# Power_Stuff.net
KiCad netlist of a schematic drawn in Altium Designer
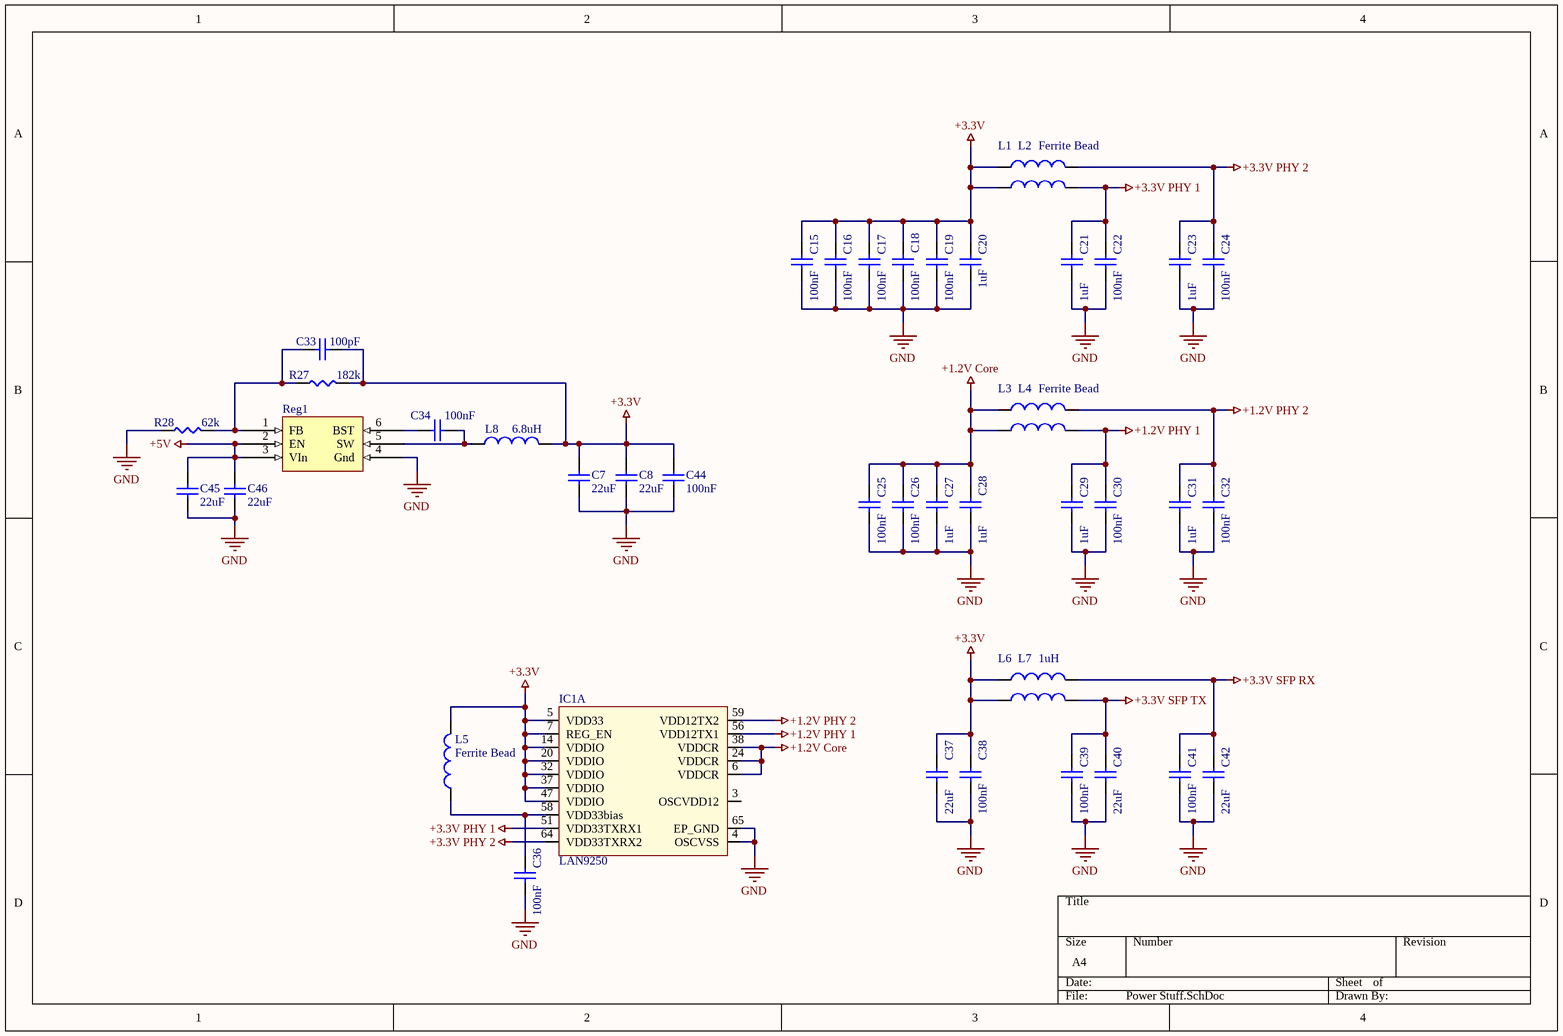
[diagram p0: Power Stuff.SchDoc]

(export (version "E")
  (design (tool "Eeschema 10.0.6"))
  (components
    (comp (ref "C7") (value "22uF") (footprint "0603") (libsource (lib "stdLib") (part "Cap")))
    (comp (ref "C8") (value "22uF") (footprint "0603") (libsource (lib "stdLib") (part "Cap")))
    (comp (ref "C15") (value "100nF") (footprint "0402") (libsource (lib "stdLib") (part "Cap")))
    (comp (ref "C16") (value "100nF") (footprint "0402") (libsource (lib "stdLib") (part "Cap")))
    (comp (ref "C17") (value "100nF") (footprint "0402") (libsource (lib "stdLib") (part "Cap")))
    (comp (ref "C18") (value "100nF") (footprint "0402") (libsource (lib "stdLib") (part "Cap")))
    (comp (ref "C19") (value "100nF") (footprint "0402") (libsource (lib "stdLib") (part "Cap")))
    (comp (ref "C20") (value "1uF") (footprint "0402") (libsource (lib "stdLib") (part "Cap")))
    (comp (ref "C21") (value "1uF") (footprint "0402") (libsource (lib "stdLib") (part "Cap")))
    (comp (ref "C22") (value "100nF") (footprint "0402") (libsource (lib "stdLib") (part "Cap")))
    (comp (ref "C23") (value "1uF") (footprint "0402") (libsource (lib "stdLib") (part "Cap")))
    (comp (ref "C24") (value "100nF") (footprint "0402") (libsource (lib "stdLib") (part "Cap")))
    (comp (ref "C25") (value "100nF") (footprint "0402") (libsource (lib "stdLib") (part "Cap")))
    (comp (ref "C26") (value "100nF") (footprint "0402") (libsource (lib "stdLib") (part "Cap")))
    (comp (ref "C27") (value "1uF") (footprint "0402") (libsource (lib "stdLib") (part "Cap")))
    (comp (ref "C28") (value "1uF") (footprint "0402") (libsource (lib "stdLib") (part "Cap")))
    (comp (ref "C29") (value "1uF") (footprint "0402") (libsource (lib "stdLib") (part "Cap")))
    (comp (ref "C30") (value "100nF") (footprint "0402") (libsource (lib "stdLib") (part "Cap")))
    (comp (ref "C31") (value "1uF") (footprint "0402") (libsource (lib "stdLib") (part "Cap")))
    (comp (ref "C32") (value "100nF") (footprint "0402") (libsource (lib "stdLib") (part "Cap")))
    (comp (ref "C33") (value "100pF") (footprint "0402") (libsource (lib "stdLib") (part "Cap")))
    (comp (ref "C34") (value "100nF") (footprint "0402") (libsource (lib "stdLib") (part "Cap")))
    (comp (ref "C36") (value "100nF") (footprint "0402") (libsource (lib "stdLib") (part "Cap")))
    (comp (ref "C37") (value "22uF") (footprint "0603") (libsource (lib "stdLib") (part "Cap")))
    (comp (ref "C38") (value "100nF") (footprint "0402") (libsource (lib "stdLib") (part "Cap")))
    (comp (ref "C39") (value "100nF") (footprint "0402") (libsource (lib "stdLib") (part "Cap")))
    (comp (ref "C40") (value "22uF") (footprint "0603") (libsource (lib "stdLib") (part "Cap")))
    (comp (ref "C41") (value "100nF") (footprint "0402") (libsource (lib "stdLib") (part "Cap")))
    (comp (ref "C42") (value "22uF") (footprint "0603") (libsource (lib "stdLib") (part "Cap")))
    (comp (ref "C44") (value "100nF") (footprint "0402") (libsource (lib "stdLib") (part "Cap")))
    (comp (ref "C45") (value "22uF") (footprint "0603") (libsource (lib "stdLib") (part "Cap")))
    (comp (ref "C46") (value "22uF") (footprint "0603") (libsource (lib "stdLib") (part "Cap")))
    (comp (ref "IC1")
      (value "LAN9250")
      (footprint "QFN64")
      (description "10/100 Ethernet controller & PHY")
      (libsource (lib "stdLib") (part "LAN9250"))
    )
    (comp (ref "L1") (value "Ferrite Bead") (footprint "0402") (libsource (lib "stdLib") (part "Inductor")))
    (comp (ref "L2") (value "Ferrite Bead") (footprint "0402") (libsource (lib "stdLib") (part "Inductor")))
    (comp (ref "L3") (value "Ferrite Bead") (footprint "0402") (libsource (lib "stdLib") (part "Inductor")))
    (comp (ref "L4") (value "Ferrite Bead") (footprint "0402") (libsource (lib "stdLib") (part "Inductor")))
    (comp (ref "L5") (value "Ferrite Bead") (footprint "0402") (libsource (lib "stdLib") (part "Inductor")))
    (comp (ref "L6") (value "1uH") (footprint "0603") (libsource (lib "stdLib") (part "Inductor")))
    (comp (ref "L7") (value "1uH") (footprint "0603") (libsource (lib "stdLib") (part "Inductor")))
    (comp (ref "L8") (value "6.8uH") (footprint "1008") (libsource (lib "stdLib") (part "Inductor")))
    (comp (ref "R27") (value "182k") (footprint "0402") (libsource (lib "stdLib") (part "Resistor")))
    (comp (ref "R28") (value "62k") (footprint "0402") (libsource (lib "stdLib") (part "Resistor")))
    (comp (ref "Reg1")
      (value "Buck regulator")
      (footprint "TSOT26")
      (libsource (lib "stdLib") (part "AP6320"))
    )
  )
  (nets
    (net (code "1") (name "+1.2V Core") (class "Default")
      (node (ref "C25") (pin "1") (pinfunction "1_1") (pintype "passive"))
      (node (ref "C26") (pin "1") (pinfunction "1_1") (pintype "passive"))
      (node (ref "C27") (pin "1") (pinfunction "1_1") (pintype "passive"))
      (node (ref "C28") (pin "1") (pinfunction "1_1") (pintype "passive"))
      (node (ref "IC1") (pin "24") (pinfunction "VDDCR_24") (pintype "passive"))
      (node (ref "IC1") (pin "38") (pinfunction "VDDCR_38") (pintype "passive"))
      (node (ref "IC1") (pin "6") (pinfunction "VDDCR_6") (pintype "passive"))
      (node (ref "L3") (pin "1") (pinfunction "1_1") (pintype "passive"))
      (node (ref "L4") (pin "1") (pinfunction "1_1") (pintype "passive"))
    )
    (net (code "2") (name "+1.2V PHY 1") (class "Default")
      (node (ref "C29") (pin "1") (pinfunction "1_1") (pintype "passive"))
      (node (ref "C30") (pin "1") (pinfunction "1_1") (pintype "passive"))
      (node (ref "IC1") (pin "56") (pinfunction "VDD12TX1_56") (pintype "passive"))
      (node (ref "L4") (pin "2") (pinfunction "2_2") (pintype "passive"))
    )
    (net (code "3") (name "+1.2V PHY 2") (class "Default")
      (node (ref "C31") (pin "1") (pinfunction "1_1") (pintype "passive"))
      (node (ref "C32") (pin "1") (pinfunction "1_1") (pintype "passive"))
      (node (ref "IC1") (pin "59") (pinfunction "VDD12TX2_59") (pintype "passive"))
      (node (ref "L3") (pin "2") (pinfunction "2_2") (pintype "passive"))
    )
    (net (code "4") (name "+3.3V") (class "Default")
      (node (ref "C15") (pin "1") (pinfunction "1_1") (pintype "passive"))
      (node (ref "C16") (pin "1") (pinfunction "1_1") (pintype "passive"))
      (node (ref "C17") (pin "1") (pinfunction "1_1") (pintype "passive"))
      (node (ref "C18") (pin "1") (pinfunction "1_1") (pintype "passive"))
      (node (ref "C19") (pin "1") (pinfunction "1_1") (pintype "passive"))
      (node (ref "C20") (pin "1") (pinfunction "1_1") (pintype "passive"))
      (node (ref "C33") (pin "1") (pinfunction "1_1") (pintype "passive"))
      (node (ref "C37") (pin "1") (pinfunction "1_1") (pintype "passive"))
      (node (ref "C38") (pin "1") (pinfunction "1_1") (pintype "passive"))
      (node (ref "C44") (pin "1") (pinfunction "1_1") (pintype "passive"))
      (node (ref "C7") (pin "1") (pinfunction "1_1") (pintype "passive"))
      (node (ref "C8") (pin "1") (pinfunction "1_1") (pintype "passive"))
      (node (ref "IC1") (pin "14") (pinfunction "VDDIO_14") (pintype "passive"))
      (node (ref "IC1") (pin "20") (pinfunction "VDDIO_20") (pintype "passive"))
      (node (ref "IC1") (pin "32") (pinfunction "VDDIO_32") (pintype "passive"))
      (node (ref "IC1") (pin "37") (pinfunction "VDDIO_37") (pintype "passive"))
      (node (ref "IC1") (pin "47") (pinfunction "VDDIO_47") (pintype "passive"))
      (node (ref "IC1") (pin "5") (pinfunction "VDD33_5") (pintype "passive"))
      (node (ref "IC1") (pin "7") (pinfunction "REG_EN_7") (pintype "passive"))
      (node (ref "L1") (pin "1") (pinfunction "1_1") (pintype "passive"))
      (node (ref "L2") (pin "1") (pinfunction "1_1") (pintype "passive"))
      (node (ref "L5") (pin "2") (pinfunction "2_2") (pintype "passive"))
      (node (ref "L6") (pin "1") (pinfunction "1_1") (pintype "passive"))
      (node (ref "L7") (pin "1") (pinfunction "1_1") (pintype "passive"))
      (node (ref "L8") (pin "2") (pinfunction "2_2") (pintype "passive"))
      (node (ref "R27") (pin "2") (pinfunction "2_2") (pintype "passive"))
    )
    (net (code "5") (name "+3.3V PHY 1") (class "Default")
      (node (ref "C21") (pin "1") (pinfunction "1_1") (pintype "passive"))
      (node (ref "C22") (pin "1") (pinfunction "1_1") (pintype "passive"))
      (node (ref "IC1") (pin "51") (pinfunction "VDD33TXRX1_51") (pintype "passive"))
      (node (ref "L2") (pin "2") (pinfunction "2_2") (pintype "passive"))
    )
    (net (code "6") (name "+3.3V PHY 2") (class "Default")
      (node (ref "C23") (pin "1") (pinfunction "1_1") (pintype "passive"))
      (node (ref "C24") (pin "1") (pinfunction "1_1") (pintype "passive"))
      (node (ref "IC1") (pin "64") (pinfunction "VDD33TXRX2_64") (pintype "passive"))
      (node (ref "L1") (pin "2") (pinfunction "2_2") (pintype "passive"))
    )
    (net (code "7") (name "+3.3V SFP RX") (class "Default")
      (node (ref "C41") (pin "1") (pinfunction "1_1") (pintype "passive"))
      (node (ref "C42") (pin "1") (pinfunction "1_1") (pintype "passive"))
      (node (ref "L6") (pin "2") (pinfunction "2_2") (pintype "passive"))
    )
    (net (code "8") (name "+3.3V SFP TX") (class "Default")
      (node (ref "C39") (pin "1") (pinfunction "1_1") (pintype "passive"))
      (node (ref "C40") (pin "1") (pinfunction "1_1") (pintype "passive"))
      (node (ref "L7") (pin "2") (pinfunction "2_2") (pintype "passive"))
    )
    (net (code "9") (name "+5V") (class "Default")
      (node (ref "C45") (pin "2") (pinfunction "2_2") (pintype "passive"))
      (node (ref "C46") (pin "1") (pinfunction "1_1") (pintype "passive"))
      (node (ref "Reg1") (pin "2") (pinfunction "EN_2") (pintype "input"))
      (node (ref "Reg1") (pin "3") (pinfunction "VIn_3") (pintype "input"))
    )
    (net (code "10") (name "GND") (class "Default")
      (node (ref "C15") (pin "2") (pinfunction "2_2") (pintype "passive"))
      (node (ref "C16") (pin "2") (pinfunction "2_2") (pintype "passive"))
      (node (ref "C17") (pin "2") (pinfunction "2_2") (pintype "passive"))
      (node (ref "C18") (pin "2") (pinfunction "2_2") (pintype "passive"))
      (node (ref "C19") (pin "2") (pinfunction "2_2") (pintype "passive"))
      (node (ref "C20") (pin "2") (pinfunction "2_2") (pintype "passive"))
      (node (ref "C21") (pin "2") (pinfunction "2_2") (pintype "passive"))
      (node (ref "C22") (pin "2") (pinfunction "2_2") (pintype "passive"))
      (node (ref "C23") (pin "2") (pinfunction "2_2") (pintype "passive"))
      (node (ref "C24") (pin "2") (pinfunction "2_2") (pintype "passive"))
      (node (ref "C25") (pin "2") (pinfunction "2_2") (pintype "passive"))
      (node (ref "C26") (pin "2") (pinfunction "2_2") (pintype "passive"))
      (node (ref "C27") (pin "2") (pinfunction "2_2") (pintype "passive"))
      (node (ref "C28") (pin "2") (pinfunction "2_2") (pintype "passive"))
      (node (ref "C29") (pin "2") (pinfunction "2_2") (pintype "passive"))
      (node (ref "C30") (pin "2") (pinfunction "2_2") (pintype "passive"))
      (node (ref "C31") (pin "2") (pinfunction "2_2") (pintype "passive"))
      (node (ref "C32") (pin "2") (pinfunction "2_2") (pintype "passive"))
      (node (ref "C36") (pin "2") (pinfunction "2_2") (pintype "passive"))
      (node (ref "C37") (pin "2") (pinfunction "2_2") (pintype "passive"))
      (node (ref "C38") (pin "2") (pinfunction "2_2") (pintype "passive"))
      (node (ref "C39") (pin "2") (pinfunction "2_2") (pintype "passive"))
      (node (ref "C40") (pin "2") (pinfunction "2_2") (pintype "passive"))
      (node (ref "C41") (pin "2") (pinfunction "2_2") (pintype "passive"))
      (node (ref "C42") (pin "2") (pinfunction "2_2") (pintype "passive"))
      (node (ref "C44") (pin "2") (pinfunction "2_2") (pintype "passive"))
      (node (ref "C45") (pin "1") (pinfunction "1_1") (pintype "passive"))
      (node (ref "C46") (pin "2") (pinfunction "2_2") (pintype "passive"))
      (node (ref "C7") (pin "2") (pinfunction "2_2") (pintype "passive"))
      (node (ref "C8") (pin "2") (pinfunction "2_2") (pintype "passive"))
      (node (ref "IC1") (pin "4") (pinfunction "OSCVSS_4") (pintype "passive"))
      (node (ref "IC1") (pin "65") (pinfunction "EP_GND_65") (pintype "passive"))
      (node (ref "R28") (pin "1") (pinfunction "1_1") (pintype "passive"))
      (node (ref "Reg1") (pin "4") (pinfunction "Gnd_4") (pintype "input"))
    )
    (net (code "11") (name "Net-(IC1A-VDD33bias)") (class "Default")
      (node (ref "C36") (pin "1") (pinfunction "1_1") (pintype "passive"))
      (node (ref "IC1") (pin "58") (pinfunction "VDD33bias_58") (pintype "passive"))
      (node (ref "L5") (pin "1") (pinfunction "1_1") (pintype "passive"))
    )
    (net (code "12") (name "Net-(Reg1-BST)") (class "Default")
      (node (ref "C34") (pin "1") (pinfunction "1_1") (pintype "passive"))
      (node (ref "Reg1") (pin "6") (pinfunction "BST_6") (pintype "input"))
    )
    (net (code "13") (name "Net-(Reg1-FB)") (class "Default")
      (node (ref "C33") (pin "2") (pinfunction "2_2") (pintype "passive"))
      (node (ref "R27") (pin "1") (pinfunction "1_1") (pintype "passive"))
      (node (ref "R28") (pin "2") (pinfunction "2_2") (pintype "passive"))
      (node (ref "Reg1") (pin "1") (pinfunction "FB_1") (pintype "input"))
    )
    (net (code "14") (name "Net-(Reg1-SW)") (class "Default")
      (node (ref "C34") (pin "2") (pinfunction "2_2") (pintype "passive"))
      (node (ref "L8") (pin "1") (pinfunction "1_1") (pintype "passive"))
      (node (ref "Reg1") (pin "5") (pinfunction "SW_5") (pintype "input"))
    )
    (net (code "15") (name "unconnected-(IC1A-OSCVDD12-Pad3)") (class "Default")
      (node (ref "IC1") (pin "3") (pinfunction "OSCVDD12_3") (pintype "passive"))
    )
  )
)
